# InterfaceGSM.net
KiCad netlist of a schematic drawn in Altium Designer
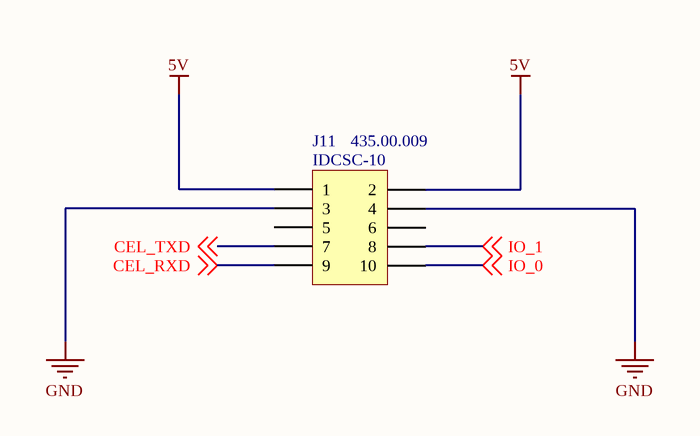
[diagram p0: InterfaceGSM.SchDoc]

(export (version "E")
  (design (tool "Eeschema 10.0.6"))
  (components
    (comp (ref "J11")
      (value "IDCSC-10")
      (footprint "IDCSC-10")
      (description "CONECTOR HEADER 10 VIAS 90º")
      (fields (field (name "ERP") "435.00.009"))
      (libsource (lib "ChaveDigital3") (part "IDCSN"))
    )
  )
  (nets
    (net (code "1") (name "5V") (class "Default")
      (node (ref "J11") (pin "1") (pinfunction "1_1") (pintype "passive"))
      (node (ref "J11") (pin "2") (pinfunction "2_2") (pintype "passive"))
    )
    (net (code "2") (name "CEL_RXD") (class "Default")
      (node (ref "J11") (pin "9") (pinfunction "9_9") (pintype "passive"))
    )
    (net (code "3") (name "CEL_TXD") (class "Default")
      (node (ref "J11") (pin "7") (pinfunction "7_7") (pintype "passive"))
    )
    (net (code "4") (name "GND") (class "Default")
      (node (ref "J11") (pin "3") (pinfunction "3_3") (pintype "passive"))
      (node (ref "J11") (pin "4") (pinfunction "4_4") (pintype "passive"))
    )
    (net (code "5") (name "IO_0") (class "Default")
      (node (ref "J11") (pin "10") (pinfunction "10_10") (pintype "passive"))
    )
    (net (code "6") (name "IO_1") (class "Default")
      (node (ref "J11") (pin "8") (pinfunction "8_8") (pintype "passive"))
    )
    (net (code "7") (name "unconnected-(J11-Pad5)") (class "Default")
      (node (ref "J11") (pin "5") (pinfunction "5_5") (pintype "passive"))
    )
    (net (code "8") (name "unconnected-(J11-Pad6)") (class "Default")
      (node (ref "J11") (pin "6") (pinfunction "6_6") (pintype "passive"))
    )
  )
)
